# 05_-_FPGA_PWR.net
KiCad netlist of a schematic drawn in Altium Designer
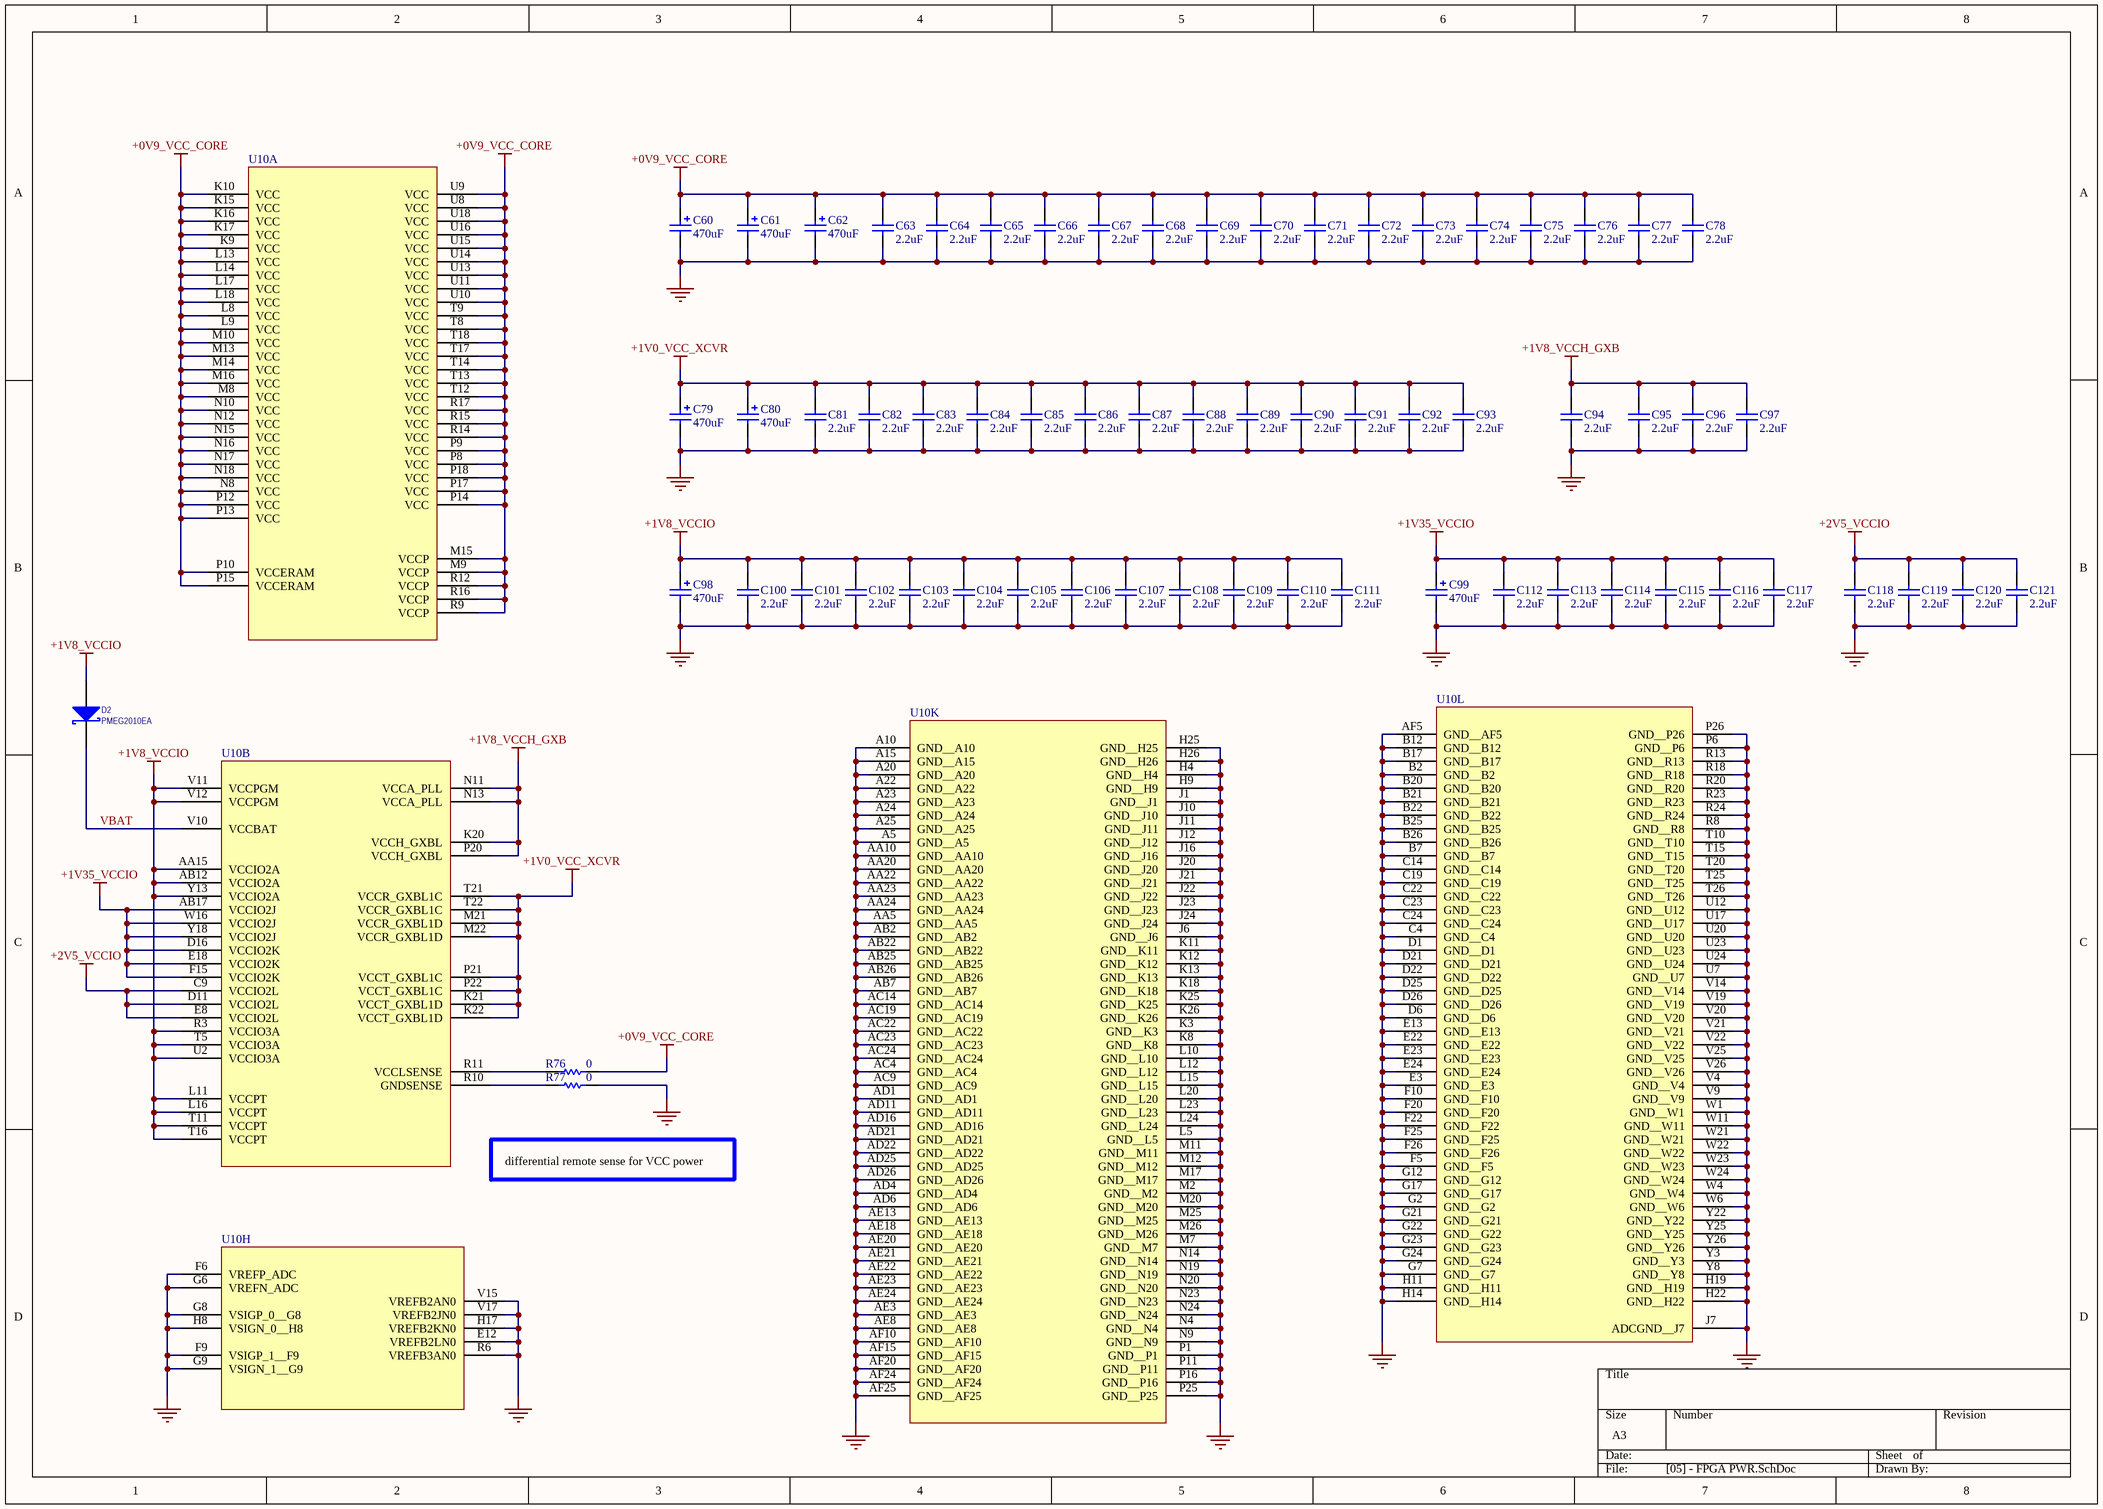
[diagram p0: [05] - FPGA PWR.SchDoc]

(export (version "E")
  (design (tool "Eeschema 10.0.6"))
  (components
    (comp (ref "C60")
      (value "470uF")
      (footprint "TANT_D")
      (description "Tantalum Polarized Capacitor")
      (fields (field (name "MANUFACTURER PART NUM") "T520D477M006ATE025"))
      (libsource (lib "Passive Components") (part "Cap Tant"))
    )
    (comp (ref "C61")
      (value "470uF")
      (footprint "TANT_D")
      (description "Tantalum Polarized Capacitor")
      (fields (field (name "MANUFACTURER PART NUM") "T520D477M006ATE025"))
      (libsource (lib "Passive Components") (part "Cap Tant"))
    )
    (comp (ref "C62")
      (value "470uF")
      (footprint "TANT_D")
      (description "Tantalum Polarized Capacitor")
      (fields (field (name "MANUFACTURER PART NUM") "T520D477M006ATE025"))
      (libsource (lib "Passive Components") (part "Cap Tant"))
    )
    (comp (ref "C63")
      (value "2.2uF")
      (footprint "0402_C")
      (description "Non-Pol SMD Capacitor")
      (fields (field (name "MANUFACTURER PART NUM") "GRM155Z71A225ME43D"))
      (libsource (lib "Passive Components") (part "Cap SMD"))
    )
    (comp (ref "C64")
      (value "2.2uF")
      (footprint "0402_C")
      (description "Non-Pol SMD Capacitor")
      (fields (field (name "MANUFACTURER PART NUM") "GRM155Z71A225ME43D"))
      (libsource (lib "Passive Components") (part "Cap SMD"))
    )
    (comp (ref "C65")
      (value "2.2uF")
      (footprint "0402_C")
      (description "Non-Pol SMD Capacitor")
      (fields (field (name "MANUFACTURER PART NUM") "GRM155Z71A225ME43D"))
      (libsource (lib "Passive Components") (part "Cap SMD"))
    )
    (comp (ref "C66")
      (value "2.2uF")
      (footprint "0402_C")
      (description "Non-Pol SMD Capacitor")
      (fields (field (name "MANUFACTURER PART NUM") "GRM155Z71A225ME43D"))
      (libsource (lib "Passive Components") (part "Cap SMD"))
    )
    (comp (ref "C67")
      (value "2.2uF")
      (footprint "0402_C")
      (description "Non-Pol SMD Capacitor")
      (fields (field (name "MANUFACTURER PART NUM") "GRM155Z71A225ME43D"))
      (libsource (lib "Passive Components") (part "Cap SMD"))
    )
    (comp (ref "C68")
      (value "2.2uF")
      (footprint "0402_C")
      (description "Non-Pol SMD Capacitor")
      (fields (field (name "MANUFACTURER PART NUM") "GRM155Z71A225ME43D"))
      (libsource (lib "Passive Components") (part "Cap SMD"))
    )
    (comp (ref "C69")
      (value "2.2uF")
      (footprint "0402_C")
      (description "Non-Pol SMD Capacitor")
      (fields (field (name "MANUFACTURER PART NUM") "GRM155Z71A225ME43D"))
      (libsource (lib "Passive Components") (part "Cap SMD"))
    )
    (comp (ref "C70")
      (value "2.2uF")
      (footprint "0402_C")
      (description "Non-Pol SMD Capacitor")
      (fields (field (name "MANUFACTURER PART NUM") "GRM155Z71A225ME43D"))
      (libsource (lib "Passive Components") (part "Cap SMD"))
    )
    (comp (ref "C71")
      (value "2.2uF")
      (footprint "0402_C")
      (description "Non-Pol SMD Capacitor")
      (fields (field (name "MANUFACTURER PART NUM") "GRM155Z71A225ME43D"))
      (libsource (lib "Passive Components") (part "Cap SMD"))
    )
    (comp (ref "C72")
      (value "2.2uF")
      (footprint "0402_C")
      (description "Non-Pol SMD Capacitor")
      (fields (field (name "MANUFACTURER PART NUM") "GRM155Z71A225ME43D"))
      (libsource (lib "Passive Components") (part "Cap SMD"))
    )
    (comp (ref "C73")
      (value "2.2uF")
      (footprint "0402_C")
      (description "Non-Pol SMD Capacitor")
      (fields (field (name "MANUFACTURER PART NUM") "GRM155Z71A225ME43D"))
      (libsource (lib "Passive Components") (part "Cap SMD"))
    )
    (comp (ref "C74")
      (value "2.2uF")
      (footprint "0402_C")
      (description "Non-Pol SMD Capacitor")
      (fields (field (name "MANUFACTURER PART NUM") "GRM155Z71A225ME43D"))
      (libsource (lib "Passive Components") (part "Cap SMD"))
    )
    (comp (ref "C75")
      (value "2.2uF")
      (footprint "0402_C")
      (description "Non-Pol SMD Capacitor")
      (fields (field (name "MANUFACTURER PART NUM") "GRM155Z71A225ME43D"))
      (libsource (lib "Passive Components") (part "Cap SMD"))
    )
    (comp (ref "C76")
      (value "2.2uF")
      (footprint "0402_C")
      (description "Non-Pol SMD Capacitor")
      (fields (field (name "MANUFACTURER PART NUM") "GRM155Z71A225ME43D"))
      (libsource (lib "Passive Components") (part "Cap SMD"))
    )
    (comp (ref "C77")
      (value "2.2uF")
      (footprint "0402_C")
      (description "Non-Pol SMD Capacitor")
      (fields (field (name "MANUFACTURER PART NUM") "GRM155Z71A225ME43D"))
      (libsource (lib "Passive Components") (part "Cap SMD"))
    )
    (comp (ref "C78")
      (value "2.2uF")
      (footprint "0402_C")
      (description "Non-Pol SMD Capacitor")
      (fields (field (name "MANUFACTURER PART NUM") "GRM155Z71A225ME43D"))
      (libsource (lib "Passive Components") (part "Cap SMD"))
    )
    (comp (ref "C79")
      (value "470uF")
      (footprint "TANT_D")
      (description "Tantalum Polarized Capacitor")
      (fields (field (name "MANUFACTURER PART NUM") "T520D477M006ATE025"))
      (libsource (lib "Passive Components") (part "Cap Tant"))
    )
    (comp (ref "C80")
      (value "470uF")
      (footprint "TANT_D")
      (description "Tantalum Polarized Capacitor")
      (fields (field (name "MANUFACTURER PART NUM") "T520D477M006ATE025"))
      (libsource (lib "Passive Components") (part "Cap Tant"))
    )
    (comp (ref "C81")
      (value "2.2uF")
      (footprint "0402_C")
      (description "Non-Pol SMD Capacitor")
      (fields (field (name "MANUFACTURER PART NUM") "GRM155Z71A225ME43D"))
      (libsource (lib "Passive Components") (part "Cap SMD"))
    )
    (comp (ref "C82")
      (value "2.2uF")
      (footprint "0402_C")
      (description "Non-Pol SMD Capacitor")
      (fields (field (name "MANUFACTURER PART NUM") "GRM155Z71A225ME43D"))
      (libsource (lib "Passive Components") (part "Cap SMD"))
    )
    (comp (ref "C83")
      (value "2.2uF")
      (footprint "0402_C")
      (description "Non-Pol SMD Capacitor")
      (fields (field (name "MANUFACTURER PART NUM") "GRM155Z71A225ME43D"))
      (libsource (lib "Passive Components") (part "Cap SMD"))
    )
    (comp (ref "C84")
      (value "2.2uF")
      (footprint "0402_C")
      (description "Non-Pol SMD Capacitor")
      (fields (field (name "MANUFACTURER PART NUM") "GRM155Z71A225ME43D"))
      (libsource (lib "Passive Components") (part "Cap SMD"))
    )
    (comp (ref "C85")
      (value "2.2uF")
      (footprint "0402_C")
      (description "Non-Pol SMD Capacitor")
      (fields (field (name "MANUFACTURER PART NUM") "GRM155Z71A225ME43D"))
      (libsource (lib "Passive Components") (part "Cap SMD"))
    )
    (comp (ref "C86")
      (value "2.2uF")
      (footprint "0402_C")
      (description "Non-Pol SMD Capacitor")
      (fields (field (name "MANUFACTURER PART NUM") "GRM155Z71A225ME43D"))
      (libsource (lib "Passive Components") (part "Cap SMD"))
    )
    (comp (ref "C87")
      (value "2.2uF")
      (footprint "0402_C")
      (description "Non-Pol SMD Capacitor")
      (fields (field (name "MANUFACTURER PART NUM") "GRM155Z71A225ME43D"))
      (libsource (lib "Passive Components") (part "Cap SMD"))
    )
    (comp (ref "C88")
      (value "2.2uF")
      (footprint "0402_C")
      (description "Non-Pol SMD Capacitor")
      (fields (field (name "MANUFACTURER PART NUM") "GRM155Z71A225ME43D"))
      (libsource (lib "Passive Components") (part "Cap SMD"))
    )
    (comp (ref "C89")
      (value "2.2uF")
      (footprint "0402_C")
      (description "Non-Pol SMD Capacitor")
      (fields (field (name "MANUFACTURER PART NUM") "GRM155Z71A225ME43D"))
      (libsource (lib "Passive Components") (part "Cap SMD"))
    )
    (comp (ref "C90")
      (value "2.2uF")
      (footprint "0402_C")
      (description "Non-Pol SMD Capacitor")
      (fields (field (name "MANUFACTURER PART NUM") "GRM155Z71A225ME43D"))
      (libsource (lib "Passive Components") (part "Cap SMD"))
    )
    (comp (ref "C91")
      (value "2.2uF")
      (footprint "0402_C")
      (description "Non-Pol SMD Capacitor")
      (fields (field (name "MANUFACTURER PART NUM") "GRM155Z71A225ME43D"))
      (libsource (lib "Passive Components") (part "Cap SMD"))
    )
    (comp (ref "C92")
      (value "2.2uF")
      (footprint "0402_C")
      (description "Non-Pol SMD Capacitor")
      (fields (field (name "MANUFACTURER PART NUM") "GRM155Z71A225ME43D"))
      (libsource (lib "Passive Components") (part "Cap SMD"))
    )
    (comp (ref "C93")
      (value "2.2uF")
      (footprint "0402_C")
      (description "Non-Pol SMD Capacitor")
      (fields (field (name "MANUFACTURER PART NUM") "GRM155Z71A225ME43D"))
      (libsource (lib "Passive Components") (part "Cap SMD"))
    )
    (comp (ref "C94")
      (value "2.2uF")
      (footprint "0402_C")
      (description "Non-Pol SMD Capacitor")
      (fields (field (name "MANUFACTURER PART NUM") "GRM155Z71A225ME43D"))
      (libsource (lib "Passive Components") (part "Cap SMD"))
    )
    (comp (ref "C95")
      (value "2.2uF")
      (footprint "0402_C")
      (description "Non-Pol SMD Capacitor")
      (fields (field (name "MANUFACTURER PART NUM") "GRM155Z71A225ME43D"))
      (libsource (lib "Passive Components") (part "Cap SMD"))
    )
    (comp (ref "C96")
      (value "2.2uF")
      (footprint "0402_C")
      (description "Non-Pol SMD Capacitor")
      (fields (field (name "MANUFACTURER PART NUM") "GRM155Z71A225ME43D"))
      (libsource (lib "Passive Components") (part "Cap SMD"))
    )
    (comp (ref "C97")
      (value "2.2uF")
      (footprint "0402_C")
      (description "Non-Pol SMD Capacitor")
      (fields (field (name "MANUFACTURER PART NUM") "GRM155Z71A225ME43D"))
      (libsource (lib "Passive Components") (part "Cap SMD"))
    )
    (comp (ref "C98")
      (value "470uF")
      (footprint "TANT_D")
      (description "Tantalum Polarized Capacitor")
      (fields (field (name "MANUFACTURER PART NUM") "T520D477M006ATE025"))
      (libsource (lib "Passive Components") (part "Cap Tant"))
    )
    (comp (ref "C99")
      (value "470uF")
      (footprint "TANT_D")
      (description "Tantalum Polarized Capacitor")
      (fields (field (name "MANUFACTURER PART NUM") "T520D477M006ATE025"))
      (libsource (lib "Passive Components") (part "Cap Tant"))
    )
    (comp (ref "C100")
      (value "2.2uF")
      (footprint "0402_C")
      (description "Non-Pol SMD Capacitor")
      (fields (field (name "MANUFACTURER PART NUM") "GRM155Z71A225ME43D"))
      (libsource (lib "Passive Components") (part "Cap SMD"))
    )
    (comp (ref "C101")
      (value "2.2uF")
      (footprint "0402_C")
      (description "Non-Pol SMD Capacitor")
      (fields (field (name "MANUFACTURER PART NUM") "GRM155Z71A225ME43D"))
      (libsource (lib "Passive Components") (part "Cap SMD"))
    )
    (comp (ref "C102")
      (value "2.2uF")
      (footprint "0402_C")
      (description "Non-Pol SMD Capacitor")
      (fields (field (name "MANUFACTURER PART NUM") "GRM155Z71A225ME43D"))
      (libsource (lib "Passive Components") (part "Cap SMD"))
    )
    (comp (ref "C103")
      (value "2.2uF")
      (footprint "0402_C")
      (description "Non-Pol SMD Capacitor")
      (fields (field (name "MANUFACTURER PART NUM") "GRM155Z71A225ME43D"))
      (libsource (lib "Passive Components") (part "Cap SMD"))
    )
    (comp (ref "C104")
      (value "2.2uF")
      (footprint "0402_C")
      (description "Non-Pol SMD Capacitor")
      (fields (field (name "MANUFACTURER PART NUM") "GRM155Z71A225ME43D"))
      (libsource (lib "Passive Components") (part "Cap SMD"))
    )
    (comp (ref "C105")
      (value "2.2uF")
      (footprint "0402_C")
      (description "Non-Pol SMD Capacitor")
      (fields (field (name "MANUFACTURER PART NUM") "GRM155Z71A225ME43D"))
      (libsource (lib "Passive Components") (part "Cap SMD"))
    )
    (comp (ref "C106")
      (value "2.2uF")
      (footprint "0402_C")
      (description "Non-Pol SMD Capacitor")
      (fields (field (name "MANUFACTURER PART NUM") "GRM155Z71A225ME43D"))
      (libsource (lib "Passive Components") (part "Cap SMD"))
    )
    (comp (ref "C107")
      (value "2.2uF")
      (footprint "0402_C")
      (description "Non-Pol SMD Capacitor")
      (fields (field (name "MANUFACTURER PART NUM") "GRM155Z71A225ME43D"))
      (libsource (lib "Passive Components") (part "Cap SMD"))
    )
    (comp (ref "C108")
      (value "2.2uF")
      (footprint "0402_C")
      (description "Non-Pol SMD Capacitor")
      (fields (field (name "MANUFACTURER PART NUM") "GRM155Z71A225ME43D"))
      (libsource (lib "Passive Components") (part "Cap SMD"))
    )
    (comp (ref "C109")
      (value "2.2uF")
      (footprint "0402_C")
      (description "Non-Pol SMD Capacitor")
      (fields (field (name "MANUFACTURER PART NUM") "GRM155Z71A225ME43D"))
      (libsource (lib "Passive Components") (part "Cap SMD"))
    )
    (comp (ref "C110")
      (value "2.2uF")
      (footprint "0402_C")
      (description "Non-Pol SMD Capacitor")
      (fields (field (name "MANUFACTURER PART NUM") "GRM155Z71A225ME43D"))
      (libsource (lib "Passive Components") (part "Cap SMD"))
    )
    (comp (ref "C111")
      (value "2.2uF")
      (footprint "0402_C")
      (description "Non-Pol SMD Capacitor")
      (fields (field (name "MANUFACTURER PART NUM") "GRM155Z71A225ME43D"))
      (libsource (lib "Passive Components") (part "Cap SMD"))
    )
    (comp (ref "C112")
      (value "2.2uF")
      (footprint "0402_C")
      (description "Non-Pol SMD Capacitor")
      (fields (field (name "MANUFACTURER PART NUM") "GRM155Z71A225ME43D"))
      (libsource (lib "Passive Components") (part "Cap SMD"))
    )
    (comp (ref "C113")
      (value "2.2uF")
      (footprint "0402_C")
      (description "Non-Pol SMD Capacitor")
      (fields (field (name "MANUFACTURER PART NUM") "GRM155Z71A225ME43D"))
      (libsource (lib "Passive Components") (part "Cap SMD"))
    )
    (comp (ref "C114")
      (value "2.2uF")
      (footprint "0402_C")
      (description "Non-Pol SMD Capacitor")
      (fields (field (name "MANUFACTURER PART NUM") "GRM155Z71A225ME43D"))
      (libsource (lib "Passive Components") (part "Cap SMD"))
    )
    (comp (ref "C115")
      (value "2.2uF")
      (footprint "0402_C")
      (description "Non-Pol SMD Capacitor")
      (fields (field (name "MANUFACTURER PART NUM") "GRM155Z71A225ME43D"))
      (libsource (lib "Passive Components") (part "Cap SMD"))
    )
    (comp (ref "C116")
      (value "2.2uF")
      (footprint "0402_C")
      (description "Non-Pol SMD Capacitor")
      (fields (field (name "MANUFACTURER PART NUM") "GRM155Z71A225ME43D"))
      (libsource (lib "Passive Components") (part "Cap SMD"))
    )
    (comp (ref "C117")
      (value "2.2uF")
      (footprint "0402_C")
      (description "Non-Pol SMD Capacitor")
      (fields (field (name "MANUFACTURER PART NUM") "GRM155Z71A225ME43D"))
      (libsource (lib "Passive Components") (part "Cap SMD"))
    )
    (comp (ref "C118")
      (value "2.2uF")
      (footprint "0402_C")
      (description "Non-Pol SMD Capacitor")
      (fields (field (name "MANUFACTURER PART NUM") "GRM155Z71A225ME43D"))
      (libsource (lib "Passive Components") (part "Cap SMD"))
    )
    (comp (ref "C119")
      (value "2.2uF")
      (footprint "0402_C")
      (description "Non-Pol SMD Capacitor")
      (fields (field (name "MANUFACTURER PART NUM") "GRM155Z71A225ME43D"))
      (libsource (lib "Passive Components") (part "Cap SMD"))
    )
    (comp (ref "C120")
      (value "2.2uF")
      (footprint "0402_C")
      (description "Non-Pol SMD Capacitor")
      (fields (field (name "MANUFACTURER PART NUM") "GRM155Z71A225ME43D"))
      (libsource (lib "Passive Components") (part "Cap SMD"))
    )
    (comp (ref "C121")
      (value "2.2uF")
      (footprint "0402_C")
      (description "Non-Pol SMD Capacitor")
      (fields (field (name "MANUFACTURER PART NUM") "GRM155Z71A225ME43D"))
      (libsource (lib "Passive Components") (part "Cap SMD"))
    )
    (comp (ref "D2")
      (value "PMEG2010EA")
      (footprint "SMA")
      (description "Schottky Diode")
      (libsource (lib "Passive Components") (part "Diode Schottky"))
    )
    (comp (ref "R76")
      (value "0")
      (footprint "0402_R")
      (description "SMD Resistor")
      (fields (field (name "TOLERANCE") "5%"))
      (libsource (lib "Passive Components") (part "Res SMD"))
    )
    (comp (ref "R77")
      (value "0")
      (footprint "0402_R")
      (description "SMD Resistor")
      (fields (field (name "TOLERANCE") "5%"))
      (libsource (lib "Passive Components") (part "Res SMD"))
    )
    (comp (ref "U10")
      (value "10AX016 F27")
      (footprint "FBGA672")
      (fields (field (name "MANUFACTURER PART NUM") "10AX016E4F27E3SG"))
      (libsource (lib "Project_schlib") (part "10AX016"))
    )
  )
  (nets
    (net (code "1") (name "+0V9_VCC_CORE") (class "Default")
      (node (ref "C60") (pin "1") (pinfunction "1_1") (pintype "passive"))
      (node (ref "C61") (pin "1") (pinfunction "1_1") (pintype "passive"))
      (node (ref "C62") (pin "1") (pinfunction "1_1") (pintype "passive"))
      (node (ref "C63") (pin "2") (pinfunction "2_2") (pintype "passive"))
      (node (ref "C64") (pin "2") (pinfunction "2_2") (pintype "passive"))
      (node (ref "C65") (pin "2") (pinfunction "2_2") (pintype "passive"))
      (node (ref "C66") (pin "2") (pinfunction "2_2") (pintype "passive"))
      (node (ref "C67") (pin "2") (pinfunction "2_2") (pintype "passive"))
      (node (ref "C68") (pin "2") (pinfunction "2_2") (pintype "passive"))
      (node (ref "C69") (pin "2") (pinfunction "2_2") (pintype "passive"))
      (node (ref "C70") (pin "2") (pinfunction "2_2") (pintype "passive"))
      (node (ref "C71") (pin "2") (pinfunction "2_2") (pintype "passive"))
      (node (ref "C72") (pin "2") (pinfunction "2_2") (pintype "passive"))
      (node (ref "C73") (pin "2") (pinfunction "2_2") (pintype "passive"))
      (node (ref "C74") (pin "2") (pinfunction "2_2") (pintype "passive"))
      (node (ref "C75") (pin "2") (pinfunction "2_2") (pintype "passive"))
      (node (ref "C76") (pin "2") (pinfunction "2_2") (pintype "passive"))
      (node (ref "C77") (pin "2") (pinfunction "2_2") (pintype "passive"))
      (node (ref "C78") (pin "2") (pinfunction "2_2") (pintype "passive"))
      (node (ref "R76") (pin "2") (pinfunction "2_2") (pintype "passive"))
      (node (ref "U10") (pin "K10") (pinfunction "VCC_K10") (pintype "power_in"))
      (node (ref "U10") (pin "K15") (pinfunction "VCC_K15") (pintype "power_in"))
      (node (ref "U10") (pin "K16") (pinfunction "VCC_K16") (pintype "power_in"))
      (node (ref "U10") (pin "K17") (pinfunction "VCC_K17") (pintype "power_in"))
      (node (ref "U10") (pin "K9") (pinfunction "VCC_K9") (pintype "power_in"))
      (node (ref "U10") (pin "L13") (pinfunction "VCC_L13") (pintype "power_in"))
      (node (ref "U10") (pin "L14") (pinfunction "VCC_L14") (pintype "power_in"))
      (node (ref "U10") (pin "L17") (pinfunction "VCC_L17") (pintype "power_in"))
      (node (ref "U10") (pin "L18") (pinfunction "VCC_L18") (pintype "power_in"))
      (node (ref "U10") (pin "L8") (pinfunction "VCC_L8") (pintype "power_in"))
      (node (ref "U10") (pin "L9") (pinfunction "VCC_L9") (pintype "power_in"))
      (node (ref "U10") (pin "M10") (pinfunction "VCC_M10") (pintype "power_in"))
      (node (ref "U10") (pin "M13") (pinfunction "VCC_M13") (pintype "power_in"))
      (node (ref "U10") (pin "M14") (pinfunction "VCC_M14") (pintype "power_in"))
      (node (ref "U10") (pin "M15") (pinfunction "VCCP_M15") (pintype "power_in"))
      (node (ref "U10") (pin "M16") (pinfunction "VCC_M16") (pintype "power_in"))
      (node (ref "U10") (pin "M8") (pinfunction "VCC_M8") (pintype "power_in"))
      (node (ref "U10") (pin "M9") (pinfunction "VCCP_M9") (pintype "power_in"))
      (node (ref "U10") (pin "N10") (pinfunction "VCC_N10") (pintype "power_in"))
      (node (ref "U10") (pin "N12") (pinfunction "VCC_N12") (pintype "power_in"))
      (node (ref "U10") (pin "N15") (pinfunction "VCC_N15") (pintype "power_in"))
      (node (ref "U10") (pin "N16") (pinfunction "VCC_N16") (pintype "power_in"))
      (node (ref "U10") (pin "N17") (pinfunction "VCC_N17") (pintype "power_in"))
      (node (ref "U10") (pin "N18") (pinfunction "VCC_N18") (pintype "power_in"))
      (node (ref "U10") (pin "N8") (pinfunction "VCC_N8") (pintype "power_in"))
      (node (ref "U10") (pin "P10") (pinfunction "VCCERAM_P10") (pintype "power_in"))
      (node (ref "U10") (pin "P12") (pinfunction "VCC_P12") (pintype "power_in"))
      (node (ref "U10") (pin "P13") (pinfunction "VCC_P13") (pintype "power_in"))
      (node (ref "U10") (pin "P14") (pinfunction "VCC_P14") (pintype "power_in"))
      (node (ref "U10") (pin "P15") (pinfunction "VCCERAM_P15") (pintype "power_in"))
      (node (ref "U10") (pin "P17") (pinfunction "VCC_P17") (pintype "power_in"))
      (node (ref "U10") (pin "P18") (pinfunction "VCC_P18") (pintype "power_in"))
      (node (ref "U10") (pin "P8") (pinfunction "VCC_P8") (pintype "power_in"))
      (node (ref "U10") (pin "P9") (pinfunction "VCC_P9") (pintype "power_in"))
      (node (ref "U10") (pin "R12") (pinfunction "VCCP_R12") (pintype "power_in"))
      (node (ref "U10") (pin "R14") (pinfunction "VCC_R14") (pintype "power_in"))
      (node (ref "U10") (pin "R15") (pinfunction "VCC_R15") (pintype "power_in"))
      (node (ref "U10") (pin "R16") (pinfunction "VCCP_R16") (pintype "power_in"))
      (node (ref "U10") (pin "R17") (pinfunction "VCC_R17") (pintype "power_in"))
      (node (ref "U10") (pin "R9") (pinfunction "VCCP_R9") (pintype "power_in"))
      (node (ref "U10") (pin "T12") (pinfunction "VCC_T12") (pintype "power_in"))
      (node (ref "U10") (pin "T13") (pinfunction "VCC_T13") (pintype "power_in"))
      (node (ref "U10") (pin "T14") (pinfunction "VCC_T14") (pintype "power_in"))
      (node (ref "U10") (pin "T17") (pinfunction "VCC_T17") (pintype "power_in"))
      (node (ref "U10") (pin "T18") (pinfunction "VCC_T18") (pintype "power_in"))
      (node (ref "U10") (pin "T8") (pinfunction "VCC_T8") (pintype "power_in"))
      (node (ref "U10") (pin "T9") (pinfunction "VCC_T9") (pintype "power_in"))
      (node (ref "U10") (pin "U10") (pinfunction "VCC_U10") (pintype "power_in"))
      (node (ref "U10") (pin "U11") (pinfunction "VCC_U11") (pintype "power_in"))
      (node (ref "U10") (pin "U13") (pinfunction "VCC_U13") (pintype "power_in"))
      (node (ref "U10") (pin "U14") (pinfunction "VCC_U14") (pintype "power_in"))
      (node (ref "U10") (pin "U15") (pinfunction "VCC_U15") (pintype "power_in"))
      (node (ref "U10") (pin "U16") (pinfunction "VCC_U16") (pintype "power_in"))
      (node (ref "U10") (pin "U18") (pinfunction "VCC_U18") (pintype "power_in"))
      (node (ref "U10") (pin "U8") (pinfunction "VCC_U8") (pintype "power_in"))
      (node (ref "U10") (pin "U9") (pinfunction "VCC_U9") (pintype "power_in"))
    )
    (net (code "2") (name "+1V0_VCC_XCVR") (class "Default")
      (node (ref "C79") (pin "1") (pinfunction "1_1") (pintype "passive"))
      (node (ref "C80") (pin "1") (pinfunction "1_1") (pintype "passive"))
      (node (ref "C81") (pin "2") (pinfunction "2_2") (pintype "passive"))
      (node (ref "C82") (pin "2") (pinfunction "2_2") (pintype "passive"))
      (node (ref "C83") (pin "2") (pinfunction "2_2") (pintype "passive"))
      (node (ref "C84") (pin "2") (pinfunction "2_2") (pintype "passive"))
      (node (ref "C85") (pin "2") (pinfunction "2_2") (pintype "passive"))
      (node (ref "C86") (pin "2") (pinfunction "2_2") (pintype "passive"))
      (node (ref "C87") (pin "2") (pinfunction "2_2") (pintype "passive"))
      (node (ref "C88") (pin "2") (pinfunction "2_2") (pintype "passive"))
      (node (ref "C89") (pin "2") (pinfunction "2_2") (pintype "passive"))
      (node (ref "C90") (pin "2") (pinfunction "2_2") (pintype "passive"))
      (node (ref "C91") (pin "2") (pinfunction "2_2") (pintype "passive"))
      (node (ref "C92") (pin "2") (pinfunction "2_2") (pintype "passive"))
      (node (ref "C93") (pin "2") (pinfunction "2_2") (pintype "passive"))
      (node (ref "U10") (pin "K21") (pinfunction "VCCT_GXBL1D_K21") (pintype "power_in"))
      (node (ref "U10") (pin "K22") (pinfunction "VCCT_GXBL1D_K22") (pintype "power_in"))
      (node (ref "U10") (pin "M21") (pinfunction "VCCR_GXBL1D_M21") (pintype "power_in"))
      (node (ref "U10") (pin "M22") (pinfunction "VCCR_GXBL1D_M22") (pintype "power_in"))
      (node (ref "U10") (pin "P21") (pinfunction "VCCT_GXBL1C_P21") (pintype "power_in"))
      (node (ref "U10") (pin "P22") (pinfunction "VCCT_GXBL1C_P22") (pintype "power_in"))
      (node (ref "U10") (pin "T21") (pinfunction "VCCR_GXBL1C_T21") (pintype "power_in"))
      (node (ref "U10") (pin "T22") (pinfunction "VCCR_GXBL1C_T22") (pintype "power_in"))
    )
    (net (code "3") (name "+1V8_VCCH_GXB") (class "Default")
      (node (ref "C94") (pin "2") (pinfunction "2_2") (pintype "passive"))
      (node (ref "C95") (pin "2") (pinfunction "2_2") (pintype "passive"))
      (node (ref "C96") (pin "2") (pinfunction "2_2") (pintype "passive"))
      (node (ref "C97") (pin "2") (pinfunction "2_2") (pintype "passive"))
      (node (ref "U10") (pin "K20") (pinfunction "VCCH_GXBL_K20") (pintype "power_in"))
      (node (ref "U10") (pin "N11") (pinfunction "VCCA_PLL_N11") (pintype "power_in"))
      (node (ref "U10") (pin "N13") (pinfunction "VCCA_PLL_N13") (pintype "power_in"))
      (node (ref "U10") (pin "P20") (pinfunction "VCCH_GXBL_P20") (pintype "power_in"))
    )
    (net (code "4") (name "+1V8_VCCIO") (class "Default")
      (node (ref "C100") (pin "2") (pinfunction "2_2") (pintype "passive"))
      (node (ref "C101") (pin "2") (pinfunction "2_2") (pintype "passive"))
      (node (ref "C102") (pin "2") (pinfunction "2_2") (pintype "passive"))
      (node (ref "C103") (pin "2") (pinfunction "2_2") (pintype "passive"))
      (node (ref "C104") (pin "2") (pinfunction "2_2") (pintype "passive"))
      (node (ref "C105") (pin "2") (pinfunction "2_2") (pintype "passive"))
      (node (ref "C106") (pin "2") (pinfunction "2_2") (pintype "passive"))
      (node (ref "C107") (pin "2") (pinfunction "2_2") (pintype "passive"))
      (node (ref "C108") (pin "2") (pinfunction "2_2") (pintype "passive"))
      (node (ref "C109") (pin "2") (pinfunction "2_2") (pintype "passive"))
      (node (ref "C110") (pin "2") (pinfunction "2_2") (pintype "passive"))
      (node (ref "C111") (pin "2") (pinfunction "2_2") (pintype "passive"))
      (node (ref "C98") (pin "1") (pinfunction "1_1") (pintype "passive"))
      (node (ref "D2") (pin "1") (pinfunction "A_1") (pintype "passive"))
      (node (ref "U10") (pin "AA15") (pinfunction "VCCIO2A_AA15") (pintype "power_in"))
      (node (ref "U10") (pin "AB12") (pinfunction "VCCIO2A_AB12") (pintype "power_in"))
      (node (ref "U10") (pin "L11") (pinfunction "VCCPT_L11") (pintype "power_in"))
      (node (ref "U10") (pin "L16") (pinfunction "VCCPT_L16") (pintype "power_in"))
      (node (ref "U10") (pin "R3") (pinfunction "VCCIO3A_R3") (pintype "power_in"))
      (node (ref "U10") (pin "T11") (pinfunction "VCCPT_T11") (pintype "power_in"))
      (node (ref "U10") (pin "T16") (pinfunction "VCCPT_T16") (pintype "power_in"))
      (node (ref "U10") (pin "T5") (pinfunction "VCCIO3A_T5") (pintype "power_in"))
      (node (ref "U10") (pin "U2") (pinfunction "VCCIO3A_U2") (pintype "power_in"))
      (node (ref "U10") (pin "V11") (pinfunction "VCCPGM_V11") (pintype "power_in"))
      (node (ref "U10") (pin "V12") (pinfunction "VCCPGM_V12") (pintype "power_in"))
      (node (ref "U10") (pin "Y13") (pinfunction "VCCIO2A_Y13") (pintype "power_in"))
    )
    (net (code "5") (name "+1V35_VCCIO") (class "Default")
      (node (ref "C112") (pin "2") (pinfunction "2_2") (pintype "passive"))
      (node (ref "C113") (pin "2") (pinfunction "2_2") (pintype "passive"))
      (node (ref "C114") (pin "2") (pinfunction "2_2") (pintype "passive"))
      (node (ref "C115") (pin "2") (pinfunction "2_2") (pintype "passive"))
      (node (ref "C116") (pin "2") (pinfunction "2_2") (pintype "passive"))
      (node (ref "C117") (pin "2") (pinfunction "2_2") (pintype "passive"))
      (node (ref "C99") (pin "1") (pinfunction "1_1") (pintype "passive"))
      (node (ref "U10") (pin "AB17") (pinfunction "VCCIO2J_AB17") (pintype "power_in"))
      (node (ref "U10") (pin "D16") (pinfunction "VCCIO2K_D16") (pintype "power_in"))
      (node (ref "U10") (pin "E18") (pinfunction "VCCIO2K_E18") (pintype "power_in"))
      (node (ref "U10") (pin "F15") (pinfunction "VCCIO2K_F15") (pintype "power_in"))
      (node (ref "U10") (pin "W16") (pinfunction "VCCIO2J_W16") (pintype "power_in"))
      (node (ref "U10") (pin "Y18") (pinfunction "VCCIO2J_Y18") (pintype "power_in"))
    )
    (net (code "6") (name "+2V5_VCCIO") (class "Default")
      (node (ref "C118") (pin "2") (pinfunction "2_2") (pintype "passive"))
      (node (ref "C119") (pin "2") (pinfunction "2_2") (pintype "passive"))
      (node (ref "C120") (pin "2") (pinfunction "2_2") (pintype "passive"))
      (node (ref "C121") (pin "2") (pinfunction "2_2") (pintype "passive"))
      (node (ref "U10") (pin "C9") (pinfunction "VCCIO2L_C9") (pintype "power_in"))
      (node (ref "U10") (pin "D11") (pinfunction "VCCIO2L_D11") (pintype "power_in"))
      (node (ref "U10") (pin "E8") (pinfunction "VCCIO2L_E8") (pintype "power_in"))
    )
    (net (code "7") (name "/VBAT") (class "Default")
      (node (ref "D2") (pin "2") (pinfunction "K_2") (pintype "passive"))
      (node (ref "U10") (pin "V10") (pinfunction "VCCBAT_V10") (pintype "power_in"))
    )
    (net (code "8") (name "GND") (class "Default")
      (node (ref "C100") (pin "1") (pinfunction "1_1") (pintype "passive"))
      (node (ref "C101") (pin "1") (pinfunction "1_1") (pintype "passive"))
      (node (ref "C102") (pin "1") (pinfunction "1_1") (pintype "passive"))
      (node (ref "C103") (pin "1") (pinfunction "1_1") (pintype "passive"))
      (node (ref "C104") (pin "1") (pinfunction "1_1") (pintype "passive"))
      (node (ref "C105") (pin "1") (pinfunction "1_1") (pintype "passive"))
      (node (ref "C106") (pin "1") (pinfunction "1_1") (pintype "passive"))
      (node (ref "C107") (pin "1") (pinfunction "1_1") (pintype "passive"))
      (node (ref "C108") (pin "1") (pinfunction "1_1") (pintype "passive"))
      (node (ref "C109") (pin "1") (pinfunction "1_1") (pintype "passive"))
      (node (ref "C110") (pin "1") (pinfunction "1_1") (pintype "passive"))
      (node (ref "C111") (pin "1") (pinfunction "1_1") (pintype "passive"))
      (node (ref "C112") (pin "1") (pinfunction "1_1") (pintype "passive"))
      (node (ref "C113") (pin "1") (pinfunction "1_1") (pintype "passive"))
      (node (ref "C114") (pin "1") (pinfunction "1_1") (pintype "passive"))
      (node (ref "C115") (pin "1") (pinfunction "1_1") (pintype "passive"))
      (node (ref "C116") (pin "1") (pinfunction "1_1") (pintype "passive"))
      (node (ref "C117") (pin "1") (pinfunction "1_1") (pintype "passive"))
      (node (ref "C118") (pin "1") (pinfunction "1_1") (pintype "passive"))
      (node (ref "C119") (pin "1") (pinfunction "1_1") (pintype "passive"))
      (node (ref "C120") (pin "1") (pinfunction "1_1") (pintype "passive"))
      (node (ref "C121") (pin "1") (pinfunction "1_1") (pintype "passive"))
      (node (ref "C60") (pin "2") (pinfunction "2_2") (pintype "passive"))
      (node (ref "C61") (pin "2") (pinfunction "2_2") (pintype "passive"))
      (node (ref "C62") (pin "2") (pinfunction "2_2") (pintype "passive"))
      (node (ref "C63") (pin "1") (pinfunction "1_1") (pintype "passive"))
      (node (ref "C64") (pin "1") (pinfunction "1_1") (pintype "passive"))
      (node (ref "C65") (pin "1") (pinfunction "1_1") (pintype "passive"))
      (node (ref "C66") (pin "1") (pinfunction "1_1") (pintype "passive"))
      (node (ref "C67") (pin "1") (pinfunction "1_1") (pintype "passive"))
      (node (ref "C68") (pin "1") (pinfunction "1_1") (pintype "passive"))
      (node (ref "C69") (pin "1") (pinfunction "1_1") (pintype "passive"))
      (node (ref "C70") (pin "1") (pinfunction "1_1") (pintype "passive"))
      (node (ref "C71") (pin "1") (pinfunction "1_1") (pintype "passive"))
      (node (ref "C72") (pin "1") (pinfunction "1_1") (pintype "passive"))
      (node (ref "C73") (pin "1") (pinfunction "1_1") (pintype "passive"))
      (node (ref "C74") (pin "1") (pinfunction "1_1") (pintype "passive"))
      (node (ref "C75") (pin "1") (pinfunction "1_1") (pintype "passive"))
      (node (ref "C76") (pin "1") (pinfunction "1_1") (pintype "passive"))
      (node (ref "C77") (pin "1") (pinfunction "1_1") (pintype "passive"))
      (node (ref "C78") (pin "1") (pinfunction "1_1") (pintype "passive"))
      (node (ref "C79") (pin "2") (pinfunction "2_2") (pintype "passive"))
      (node (ref "C80") (pin "2") (pinfunction "2_2") (pintype "passive"))
      (node (ref "C81") (pin "1") (pinfunction "1_1") (pintype "passive"))
      (node (ref "C82") (pin "1") (pinfunction "1_1") (pintype "passive"))
      (node (ref "C83") (pin "1") (pinfunction "1_1") (pintype "passive"))
      (node (ref "C84") (pin "1") (pinfunction "1_1") (pintype "passive"))
      (node (ref "C85") (pin "1") (pinfunction "1_1") (pintype "passive"))
      (node (ref "C86") (pin "1") (pinfunction "1_1") (pintype "passive"))
      (node (ref "C87") (pin "1") (pinfunction "1_1") (pintype "passive"))
      (node (ref "C88") (pin "1") (pinfunction "1_1") (pintype "passive"))
      (node (ref "C89") (pin "1") (pinfunction "1_1") (pintype "passive"))
      (node (ref "C90") (pin "1") (pinfunction "1_1") (pintype "passive"))
      (node (ref "C91") (pin "1") (pinfunction "1_1") (pintype "passive"))
      (node (ref "C92") (pin "1") (pinfunction "1_1") (pintype "passive"))
      (node (ref "C93") (pin "1") (pinfunction "1_1") (pintype "passive"))
      (node (ref "C94") (pin "1") (pinfunction "1_1") (pintype "passive"))
      (node (ref "C95") (pin "1") (pinfunction "1_1") (pintype "passive"))
      (node (ref "C96") (pin "1") (pinfunction "1_1") (pintype "passive"))
      (node (ref "C97") (pin "1") (pinfunction "1_1") (pintype "passive"))
      (node (ref "C98") (pin "2") (pinfunction "2_2") (pintype "passive"))
      (node (ref "C99") (pin "2") (pinfunction "2_2") (pintype "passive"))
      (node (ref "R77") (pin "2") (pinfunction "2_2") (pintype "passive"))
      (node (ref "U10") (pin "A10") (pinfunction "GND__A10_A10") (pintype "power_in"))
      (node (ref "U10") (pin "A15") (pinfunction "GND__A15_A15") (pintype "power_in"))
      (node (ref "U10") (pin "A20") (pinfunction "GND__A20_A20") (pintype "power_in"))
      (node (ref "U10") (pin "A22") (pinfunction "GND__A22_A22") (pintype "power_in"))
      (node (ref "U10") (pin "A23") (pinfunction "GND__A23_A23") (pintype "power_in"))
      (node (ref "U10") (pin "A24") (pinfunction "GND__A24_A24") (pintype "power_in"))
      (node (ref "U10") (pin "A25") (pinfunction "GND__A25_A25") (pintype "power_in"))
      (node (ref "U10") (pin "A5") (pinfunction "GND__A5_A5") (pintype "power_in"))
      (node (ref "U10") (pin "AA10") (pinfunction "GND__AA10_AA10") (pintype "power_in"))
      (node (ref "U10") (pin "AA20") (pinfunction "GND__AA20_AA20") (pintype "power_in"))
      (node (ref "U10") (pin "AA22") (pinfunction "GND__AA22_AA22") (pintype "power_in"))
      (node (ref "U10") (pin "AA23") (pinfunction "GND__AA23_AA23") (pintype "power_in"))
      (node (ref "U10") (pin "AA24") (pinfunction "GND__AA24_AA24") (pintype "power_in"))
      (node (ref "U10") (pin "AA5") (pinfunction "GND__AA5_AA5") (pintype "power_in"))
      (node (ref "U10") (pin "AB2") (pinfunction "GND__AB2_AB2") (pintype "power_in"))
      (node (ref "U10") (pin "AB22") (pinfunction "GND__AB22_AB22") (pintype "power_in"))
      (node (ref "U10") (pin "AB25") (pinfunction "GND__AB25_AB25") (pintype "power_in"))
      (node (ref "U10") (pin "AB26") (pinfunction "GND__AB26_AB26") (pintype "power_in"))
      (node (ref "U10") (pin "AB7") (pinfunction "GND__AB7_AB7") (pintype "power_in"))
      (node (ref "U10") (pin "AC14") (pinfunction "GND__AC14_AC14") (pintype "power_in"))
      (node (ref "U10") (pin "AC19") (pinfunction "GND__AC19_AC19") (pintype "power_in"))
      (node (ref "U10") (pin "AC22") (pinfunction "GND__AC22_AC22") (pintype "power_in"))
      (node (ref "U10") (pin "AC23") (pinfunction "GND__AC23_AC23") (pintype "power_in"))
      (node (ref "U10") (pin "AC24") (pinfunction "GND__AC24_AC24") (pintype "power_in"))
      (node (ref "U10") (pin "AC4") (pinfunction "GND__AC4_AC4") (pintype "power_in"))
      (node (ref "U10") (pin "AC9") (pinfunction "GND__AC9_AC9") (pintype "power_in"))
      (node (ref "U10") (pin "AD1") (pinfunction "GND__AD1_AD1") (pintype "power_in"))
      (node (ref "U10") (pin "AD11") (pinfunction "GND__AD11_AD11") (pintype "power_in"))
      (node (ref "U10") (pin "AD16") (pinfunction "GND__AD16_AD16") (pintype "power_in"))
      (node (ref "U10") (pin "AD21") (pinfunction "GND__AD21_AD21") (pintype "power_in"))
      (node (ref "U10") (pin "AD22") (pinfunction "GND__AD22_AD22") (pintype "power_in"))
      (node (ref "U10") (pin "AD25") (pinfunction "GND__AD25_AD25") (pintype "power_in"))
      (node (ref "U10") (pin "AD26") (pinfunction "GND__AD26_AD26") (pintype "power_in"))
      (node (ref "U10") (pin "AD4") (pinfunction "GND__AD4_AD4") (pintype "power_in"))
      (node (ref "U10") (pin "AD6") (pinfunction "GND__AD6_AD6") (pintype "power_in"))
      (node (ref "U10") (pin "AE13") (pinfunction "GND__AE13_AE13") (pintype "power_in"))
      (node (ref "U10") (pin "AE18") (pinfunction "GND__AE18_AE18") (pintype "power_in"))
      (node (ref "U10") (pin "AE20") (pinfunction "GND__AE20_AE20") (pintype "power_in"))
      (node (ref "U10") (pin "AE21") (pinfunction "GND__AE21_AE21") (pintype "power_in"))
      (node (ref "U10") (pin "AE22") (pinfunction "GND__AE22_AE22") (pintype "power_in"))
      (node (ref "U10") (pin "AE23") (pinfunction "GND__AE23_AE23") (pintype "power_in"))
      (node (ref "U10") (pin "AE24") (pinfunction "GND__AE24_AE24") (pintype "power_in"))
      (node (ref "U10") (pin "AE3") (pinfunction "GND__AE3_AE3") (pintype "power_in"))
      (node (ref "U10") (pin "AE8") (pinfunction "GND__AE8_AE8") (pintype "power_in"))
      (node (ref "U10") (pin "AF10") (pinfunction "GND__AF10_AF10") (pintype "power_in"))
      (node (ref "U10") (pin "AF15") (pinfunction "GND__AF15_AF15") (pintype "power_in"))
      (node (ref "U10") (pin "AF20") (pinfunction "GND__AF20_AF20") (pintype "power_in"))
      (node (ref "U10") (pin "AF24") (pinfunction "GND__AF24_AF24") (pintype "power_in"))
      (node (ref "U10") (pin "AF25") (pinfunction "GND__AF25_AF25") (pintype "power_in"))
      (node (ref "U10") (pin "AF5") (pinfunction "GND__AF5_AF5") (pintype "power_in"))
      (node (ref "U10") (pin "B12") (pinfunction "GND__B12_B12") (pintype "power_in"))
      (node (ref "U10") (pin "B17") (pinfunction "GND__B17_B17") (pintype "power_in"))
      (node (ref "U10") (pin "B2") (pinfunction "GND__B2_B2") (pintype "power_in"))
      (node (ref "U10") (pin "B20") (pinfunction "GND__B20_B20") (pintype "power_in"))
      (node (ref "U10") (pin "B21") (pinfunction "GND__B21_B21") (pintype "power_in"))
      (node (ref "U10") (pin "B22") (pinfunction "GND__B22_B22") (pintype "power_in"))
      (node (ref "U10") (pin "B25") (pinfunction "GND__B25_B25") (pintype "power_in"))
      (node (ref "U10") (pin "B26") (pinfunction "GND__B26_B26") (pintype "power_in"))
      (node (ref "U10") (pin "B7") (pinfunction "GND__B7_B7") (pintype "power_in"))
      (node (ref "U10") (pin "C14") (pinfunction "GND__C14_C14") (pintype "power_in"))
      (node (ref "U10") (pin "C19") (pinfunction "GND__C19_C19") (pintype "power_in"))
      (node (ref "U10") (pin "C22") (pinfunction "GND__C22_C22") (pintype "power_in"))
      (node (ref "U10") (pin "C23") (pinfunction "GND__C23_C23") (pintype "power_in"))
      (node (ref "U10") (pin "C24") (pinfunction "GND__C24_C24") (pintype "power_in"))
      (node (ref "U10") (pin "C4") (pinfunction "GND__C4_C4") (pintype "power_in"))
      (node (ref "U10") (pin "D1") (pinfunction "GND__D1_D1") (pintype "power_in"))
      (node (ref "U10") (pin "D21") (pinfunction "GND__D21_D21") (pintype "power_in"))
      (node (ref "U10") (pin "D22") (pinfunction "GND__D22_D22") (pintype "power_in"))
      (node (ref "U10") (pin "D25") (pinfunction "GND__D25_D25") (pintype "power_in"))
      (node (ref "U10") (pin "D26") (pinfunction "GND__D26_D26") (pintype "power_in"))
      (node (ref "U10") (pin "D6") (pinfunction "GND__D6_D6") (pintype "power_in"))
      (node (ref "U10") (pin "E12") (pinfunction "VREFB2LN0_E12") (pintype "power_in"))
      (node (ref "U10") (pin "E13") (pinfunction "GND__E13_E13") (pintype "power_in"))
      (node (ref "U10") (pin "E22") (pinfunction "GND__E22_E22") (pintype "power_in"))
      (node (ref "U10") (pin "E23") (pinfunction "GND__E23_E23") (pintype "power_in"))
      (node (ref "U10") (pin "E24") (pinfunction "GND__E24_E24") (pintype "power_in"))
      (node (ref "U10") (pin "E3") (pinfunction "GND__E3_E3") (pintype "power_in"))
      (node (ref "U10") (pin "F10") (pinfunction "GND__F10_F10") (pintype "power_in"))
      (node (ref "U10") (pin "F20") (pinfunction "GND__F20_F20") (pintype "power_in"))
      (node (ref "U10") (pin "F22") (pinfunction "GND__F22_F22") (pintype "power_in"))
      (node (ref "U10") (pin "F25") (pinfunction "GND__F25_F25") (pintype "power_in"))
      (node (ref "U10") (pin "F26") (pinfunction "GND__F26_F26") (pintype "power_in"))
      (node (ref "U10") (pin "F5") (pinfunction "GND__F5_F5") (pintype "power_in"))
      (node (ref "U10") (pin "F6") (pinfunction "VREFP_ADC_F6") (pintype "power_in"))
      (node (ref "U10") (pin "F9") (pinfunction "VSIGP_1__F9_F9") (pintype "passive"))
      (node (ref "U10") (pin "G12") (pinfunction "GND__G12_G12") (pintype "power_in"))
      (node (ref "U10") (pin "G17") (pinfunction "GND__G17_G17") (pintype "power_in"))
      (node (ref "U10") (pin "G2") (pinfunction "GND__G2_G2") (pintype "power_in"))
      (node (ref "U10") (pin "G21") (pinfunction "GND__G21_G21") (pintype "power_in"))
      (node (ref "U10") (pin "G22") (pinfunction "GND__G22_G22") (pintype "power_in"))
      (node (ref "U10") (pin "G23") (pinfunction "GND__G23_G23") (pintype "power_in"))
      (node (ref "U10") (pin "G24") (pinfunction "GND__G24_G24") (pintype "power_in"))
      (node (ref "U10") (pin "G6") (pinfunction "VREFN_ADC_G6") (pintype "power_in"))
      (node (ref "U10") (pin "G7") (pinfunction "GND__G7_G7") (pintype "power_in"))
      (node (ref "U10") (pin "G8") (pinfunction "VSIGP_0__G8_G8") (pintype "passive"))
      (node (ref "U10") (pin "G9") (pinfunction "VSIGN_1__G9_G9") (pintype "passive"))
      (node (ref "U10") (pin "H11") (pinfunction "GND__H11_H11") (pintype "power_in"))
      (node (ref "U10") (pin "H14") (pinfunction "GND__H14_H14") (pintype "power_in"))
      (node (ref "U10") (pin "H17") (pinfunction "VREFB2KN0_H17") (pintype "power_in"))
      (node (ref "U10") (pin "H19") (pinfunction "GND__H19_H19") (pintype "power_in"))
      (node (ref "U10") (pin "H22") (pinfunction "GND__H22_H22") (pintype "power_in"))
      (node (ref "U10") (pin "H25") (pinfunction "GND__H25_H25") (pintype "power_in"))
      (node (ref "U10") (pin "H26") (pinfunction "GND__H26_H26") (pintype "power_in"))
      (node (ref "U10") (pin "H4") (pinfunction "GND__H4_H4") (pintype "power_in"))
      (node (ref "U10") (pin "H8") (pinfunction "VSIGN_0__H8_H8") (pintype "passive"))
      (node (ref "U10") (pin "H9") (pinfunction "GND__H9_H9") (pintype "power_in"))
      (node (ref "U10") (pin "J1") (pinfunction "GND__J1_J1") (pintype "power_in"))
      (node (ref "U10") (pin "J10") (pinfunction "GND__J10_J10") (pintype "power_in"))
      (node (ref "U10") (pin "J11") (pinfunction "GND__J11_J11") (pintype "power_in"))
      (node (ref "U10") (pin "J12") (pinfunction "GND__J12_J12") (pintype "power_in"))
      (node (ref "U10") (pin "J16") (pinfunction "GND__J16_J16") (pintype "power_in"))
      (node (ref "U10") (pin "J20") (pinfunction "GND__J20_J20") (pintype "power_in"))
      (node (ref "U10") (pin "J21") (pinfunction "GND__J21_J21") (pintype "power_in"))
      (node (ref "U10") (pin "J22") (pinfunction "GND__J22_J22") (pintype "power_in"))
      (node (ref "U10") (pin "J23") (pinfunction "GND__J23_J23") (pintype "power_in"))
      (node (ref "U10") (pin "J24") (pinfunction "GND__J24_J24") (pintype "power_in"))
      (node (ref "U10") (pin "J6") (pinfunction "GND__J6_J6") (pintype "power_in"))
      (node (ref "U10") (pin "J7") (pinfunction "ADCGND__J7_J7") (pintype "power_in"))
      (node (ref "U10") (pin "K11") (pinfunction "GND__K11_K11") (pintype "power_in"))
      (node (ref "U10") (pin "K12") (pinfunction "GND__K12_K12") (pintype "power_in"))
      (node (ref "U10") (pin "K13") (pinfunction "GND__K13_K13") (pintype "power_in"))
      (node (ref "U10") (pin "K18") (pinfunction "GND__K18_K18") (pintype "power_in"))
      (node (ref "U10") (pin "K25") (pinfunction "GND__K25_K25") (pintype "power_in"))
      (node (ref "U10") (pin "K26") (pinfunction "GND__K26_K26") (pintype "power_in"))
      (node (ref "U10") (pin "K3") (pinfunction "GND__K3_K3") (pintype "power_in"))
      (node (ref "U10") (pin "K8") (pinfunction "GND__K8_K8") (pintype "power_in"))
      (node (ref "U10") (pin "L10") (pinfunction "GND__L10_L10") (pintype "power_in"))
      (node (ref "U10") (pin "L12") (pinfunction "GND__L12_L12") (pintype "power_in"))
      (node (ref "U10") (pin "L15") (pinfunction "GND__L15_L15") (pintype "power_in"))
      (node (ref "U10") (pin "L20") (pinfunction "GND__L20_L20") (pintype "power_in"))
      (node (ref "U10") (pin "L23") (pinfunction "GND__L23_L23") (pintype "power_in"))
      (node (ref "U10") (pin "L24") (pinfunction "GND__L24_L24") (pintype "power_in"))
      (node (ref "U10") (pin "L5") (pinfunction "GND__L5_L5") (pintype "power_in"))
      (node (ref "U10") (pin "M11") (pinfunction "GND__M11_M11") (pintype "power_in"))
      (node (ref "U10") (pin "M12") (pinfunction "GND__M12_M12") (pintype "power_in"))
      (node (ref "U10") (pin "M17") (pinfunction "GND__M17_M17") (pintype "power_in"))
      (node (ref "U10") (pin "M2") (pinfunction "GND__M2_M2") (pintype "power_in"))
      (node (ref "U10") (pin "M20") (pinfunction "GND__M20_M20") (pintype "power_in"))
      (node (ref "U10") (pin "M25") (pinfunction "GND__M25_M25") (pintype "power_in"))
      (node (ref "U10") (pin "M26") (pinfunction "GND__M26_M26") (pintype "power_in"))
      (node (ref "U10") (pin "M7") (pinfunction "GND__M7_M7") (pintype "power_in"))
      (node (ref "U10") (pin "N14") (pinfunction "GND__N14_N14") (pintype "power_in"))
      (node (ref "U10") (pin "N19") (pinfunction "GND__N19_N19") (pintype "power_in"))
      (node (ref "U10") (pin "N20") (pinfunction "GND__N20_N20") (pintype "power_in"))
      (node (ref "U10") (pin "N23") (pinfunction "GND__N23_N23") (pintype "power_in"))
      (node (ref "U10") (pin "N24") (pinfunction "GND__N24_N24") (pintype "power_in"))
      (node (ref "U10") (pin "N4") (pinfunction "GND__N4_N4") (pintype "power_in"))
      (node (ref "U10") (pin "N9") (pinfunction "GND__N9_N9") (pintype "power_in"))
      (node (ref "U10") (pin "P1") (pinfunction "GND__P1_P1") (pintype "power_in"))
      (node (ref "U10") (pin "P11") (pinfunction "GND__P11_P11") (pintype "power_in"))
      (node (ref "U10") (pin "P16") (pinfunction "GND__P16_P16") (pintype "power_in"))
      (node (ref "U10") (pin "P25") (pinfunction "GND__P25_P25") (pintype "power_in"))
      (node (ref "U10") (pin "P26") (pinfunction "GND__P26_P26") (pintype "power_in"))
      (node (ref "U10") (pin "P6") (pinfunction "GND__P6_P6") (pintype "power_in"))
      (node (ref "U10") (pin "R13") (pinfunction "GND__R13_R13") (pintype "power_in"))
      (node (ref "U10") (pin "R18") (pinfunction "GND__R18_R18") (pintype "power_in"))
      (node (ref "U10") (pin "R20") (pinfunction "GND__R20_R20") (pintype "power_in"))
      (node (ref "U10") (pin "R23") (pinfunction "GND__R23_R23") (pintype "power_in"))
      (node (ref "U10") (pin "R24") (pinfunction "GND__R24_R24") (pintype "power_in"))
      (node (ref "U10") (pin "R6") (pinfunction "VREFB3AN0_R6") (pintype "power_in"))
      (node (ref "U10") (pin "R8") (pinfunction "GND__R8_R8") (pintype "power_in"))
      (node (ref "U10") (pin "T10") (pinfunction "GND__T10_T10") (pintype "power_in"))
      (node (ref "U10") (pin "T15") (pinfunction "GND__T15_T15") (pintype "power_in"))
      (node (ref "U10") (pin "T20") (pinfunction "GND__T20_T20") (pintype "power_in"))
      (node (ref "U10") (pin "T25") (pinfunction "GND__T25_T25") (pintype "power_in"))
      (node (ref "U10") (pin "T26") (pinfunction "GND__T26_T26") (pintype "power_in"))
      (node (ref "U10") (pin "U12") (pinfunction "GND__U12_U12") (pintype "power_in"))
      (node (ref "U10") (pin "U17") (pinfunction "GND__U17_U17") (pintype "power_in"))
      (node (ref "U10") (pin "U20") (pinfunction "GND__U20_U20") (pintype "power_in"))
      (node (ref "U10") (pin "U23") (pinfunction "GND__U23_U23") (pintype "power_in"))
      (node (ref "U10") (pin "U24") (pinfunction "GND__U24_U24") (pintype "power_in"))
      (node (ref "U10") (pin "U7") (pinfunction "GND__U7_U7") (pintype "power_in"))
      (node (ref "U10") (pin "V14") (pinfunction "GND__V14_V14") (pintype "power_in"))
      (node (ref "U10") (pin "V15") (pinfunction "VREFB2AN0_V15") (pintype "power_in"))
      (node (ref "U10") (pin "V17") (pinfunction "VREFB2JN0_V17") (pintype "power_in"))
      (node (ref "U10") (pin "V19") (pinfunction "GND__V19_V19") (pintype "power_in"))
      (node (ref "U10") (pin "V20") (pinfunction "GND__V20_V20") (pintype "power_in"))
      (node (ref "U10") (pin "V21") (pinfunction "GND__V21_V21") (pintype "power_in"))
      (node (ref "U10") (pin "V22") (pinfunction "GND__V22_V22") (pintype "power_in"))
      (node (ref "U10") (pin "V25") (pinfunction "GND__V25_V25") (pintype "power_in"))
      (node (ref "U10") (pin "V26") (pinfunction "GND__V26_V26") (pintype "power_in"))
      (node (ref "U10") (pin "V4") (pinfunction "GND__V4_V4") (pintype "power_in"))
      (node (ref "U10") (pin "V9") (pinfunction "GND__V9_V9") (pintype "power_in"))
      (node (ref "U10") (pin "W1") (pinfunction "GND__W1_W1") (pintype "power_in"))
      (node (ref "U10") (pin "W11") (pinfunction "GND__W11_W11") (pintype "power_in"))
      (node (ref "U10") (pin "W21") (pinfunction "GND__W21_W21") (pintype "power_in"))
      (node (ref "U10") (pin "W22") (pinfunction "GND__W22_W22") (pintype "power_in"))
      (node (ref "U10") (pin "W23") (pinfunction "GND__W23_W23") (pintype "power_in"))
      (node (ref "U10") (pin "W24") (pinfunction "GND__W24_W24") (pintype "power_in"))
      (node (ref "U10") (pin "W4") (pinfunction "GND__W4_W4") (pintype "power_in"))
      (node (ref "U10") (pin "W6") (pinfunction "GND__W6_W6") (pintype "power_in"))
      (node (ref "U10") (pin "Y22") (pinfunction "GND__Y22_Y22") (pintype "power_in"))
      (node (ref "U10") (pin "Y25") (pinfunction "GND__Y25_Y25") (pintype "power_in"))
      (node (ref "U10") (pin "Y26") (pinfunction "GND__Y26_Y26") (pintype "power_in"))
      (node (ref "U10") (pin "Y3") (pinfunction "GND__Y3_Y3") (pintype "power_in"))
      (node (ref "U10") (pin "Y8") (pinfunction "GND__Y8_Y8") (pintype "power_in"))
    )
    (net (code "9") (name "Net-(U10B-GNDSENSE)") (class "Default")
      (node (ref "R77") (pin "1") (pinfunction "1_1") (pintype "passive"))
      (node (ref "U10") (pin "R10") (pinfunction "GNDSENSE_R10") (pintype "power_in"))
    )
    (net (code "10") (name "Net-(U10B-VCCLSENSE)") (class "Default")
      (node (ref "R76") (pin "1") (pinfunction "1_1") (pintype "passive"))
      (node (ref "U10") (pin "R11") (pinfunction "VCCLSENSE_R11") (pintype "power_in"))
    )
  )
)
